# quad87.net
KiCad netlist of a schematic drawn in EAGLE
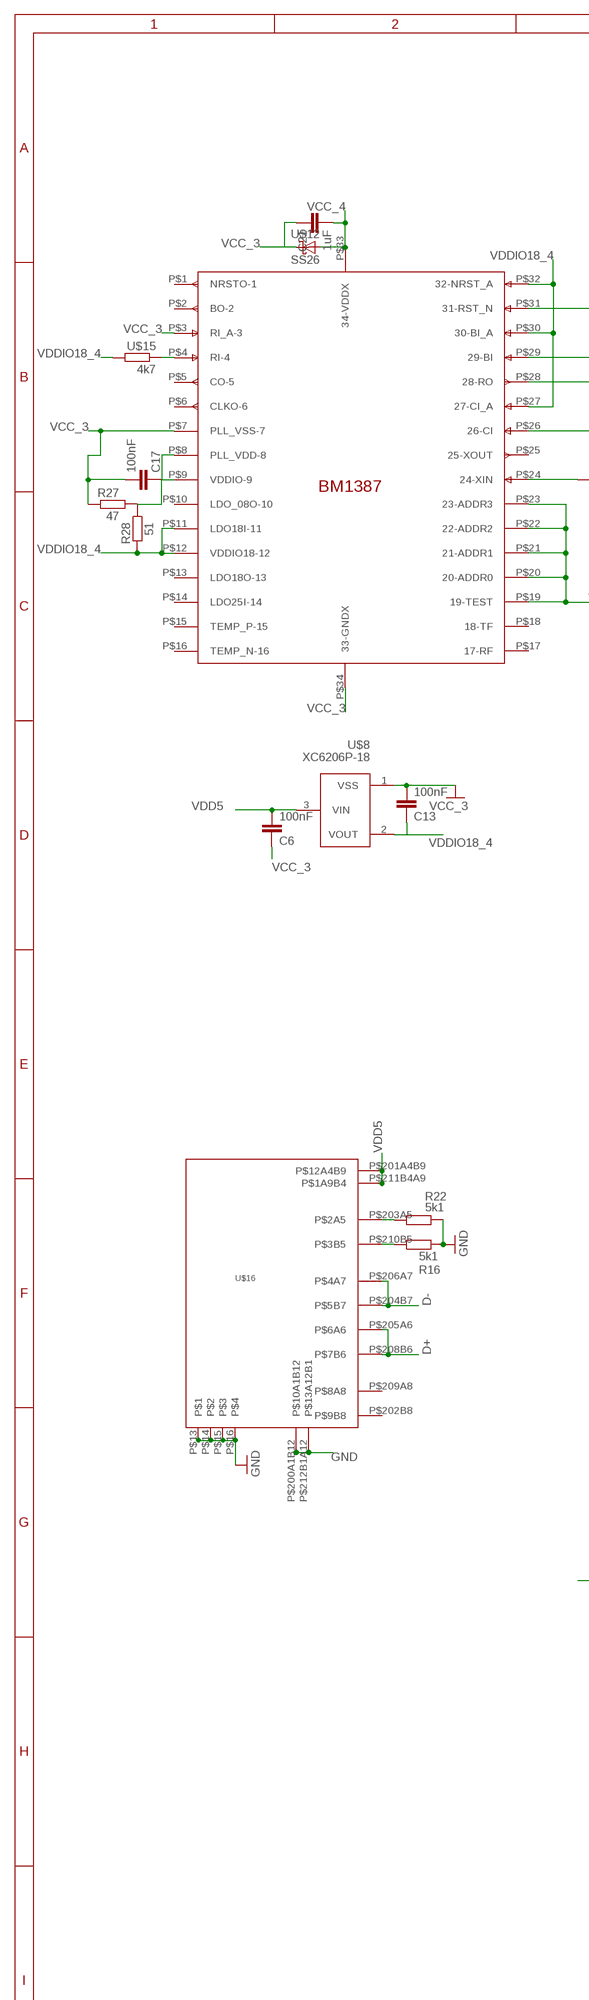
[diagram p0: schematic, sheet 1, part 1 of 2]
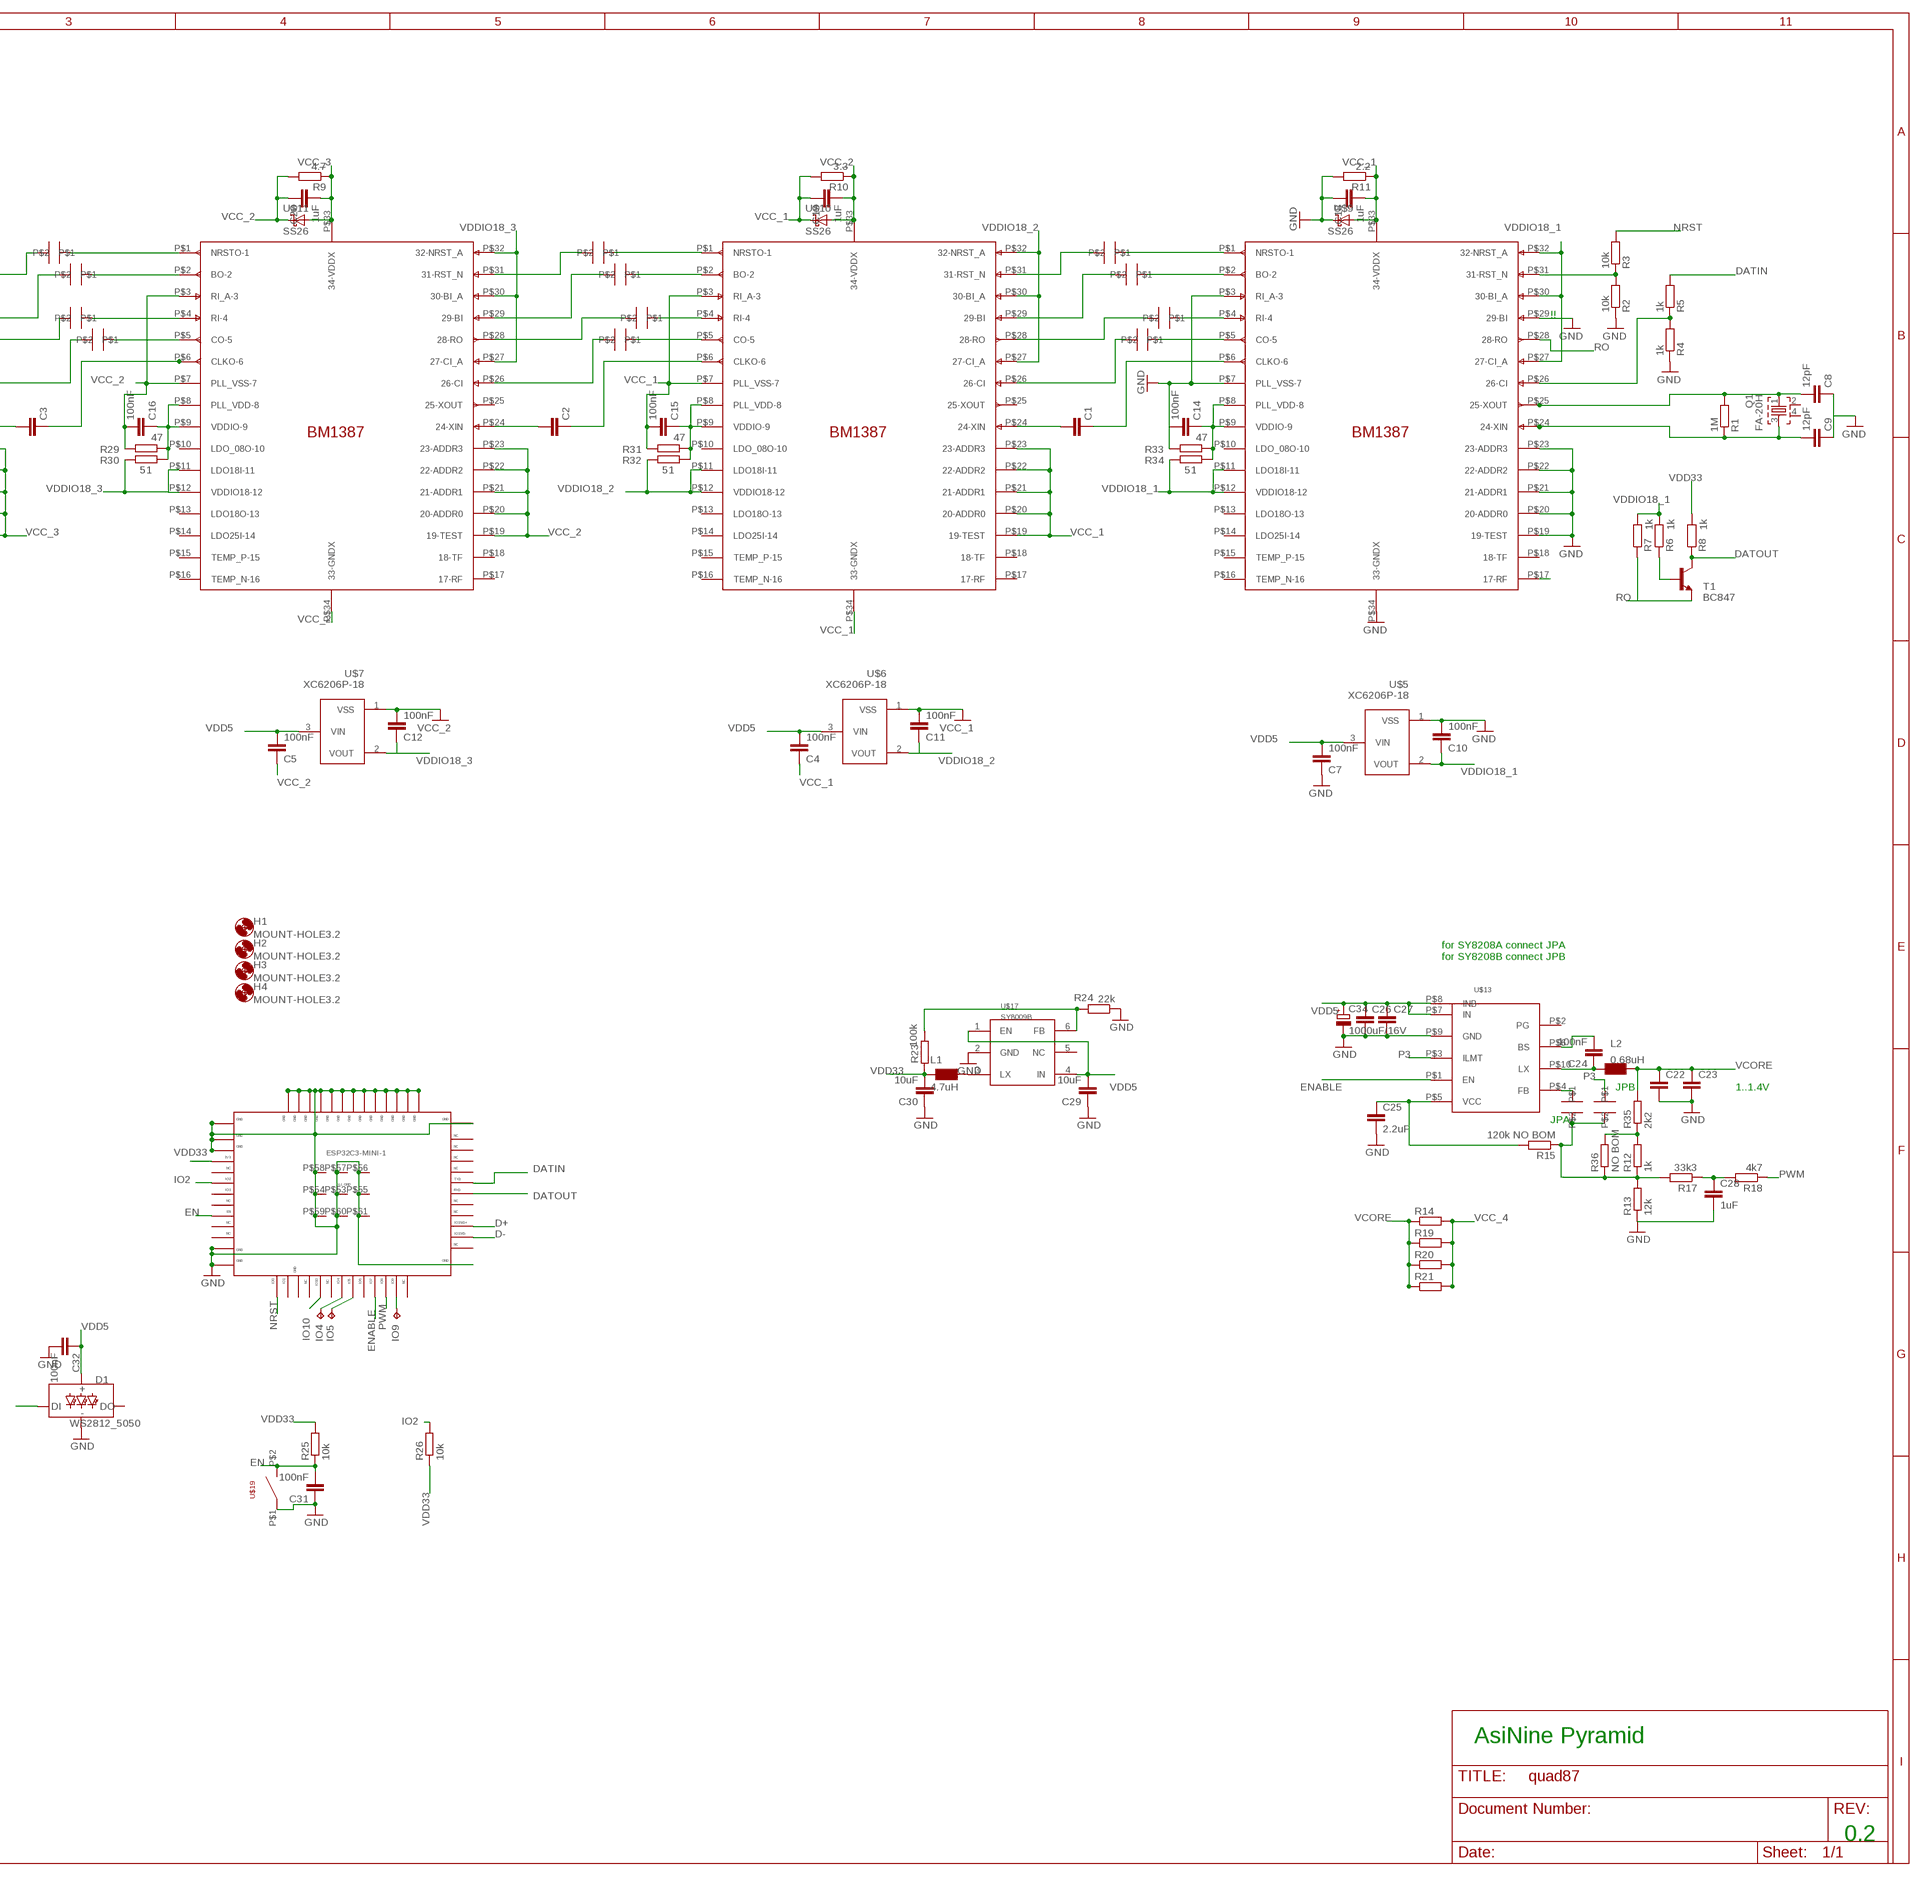
[diagram p1: schematic, sheet 1, part 2 of 2]

(export (version "E")
  (design (tool "Eeschema 10.0.6"))
  (components
    (comp (ref "C1")
      (value "C-EUC0402")
      (footprint "eagle-import:C0402")
      (libsource (lib "eagle-import") (part "C-EUC0402"))
    )
    (comp (ref "C2")
      (value "C-EUC0402")
      (footprint "eagle-import:C0402")
      (libsource (lib "eagle-import") (part "C-EUC0402"))
    )
    (comp (ref "C3")
      (value "C-EUC0402")
      (footprint "eagle-import:C0402")
      (libsource (lib "eagle-import") (part "C-EUC0402"))
    )
    (comp (ref "C4")
      (value "100nF")
      (footprint "eagle-import:C0603")
      (libsource (lib "eagle-import") (part "C-EUC0603"))
    )
    (comp (ref "C5")
      (value "100nF")
      (footprint "eagle-import:C0603")
      (libsource (lib "eagle-import") (part "C-EUC0603"))
    )
    (comp (ref "C6")
      (value "100nF")
      (footprint "eagle-import:C0603")
      (libsource (lib "eagle-import") (part "C-EUC0603"))
    )
    (comp (ref "C7")
      (value "100nF")
      (footprint "eagle-import:C0603")
      (libsource (lib "eagle-import") (part "C-EUC0603"))
    )
    (comp (ref "C8")
      (value "12pF")
      (footprint "eagle-import:C0402")
      (libsource (lib "eagle-import") (part "C-EUC0402"))
    )
    (comp (ref "C9")
      (value "12pF")
      (footprint "eagle-import:C0402")
      (libsource (lib "eagle-import") (part "C-EUC0402"))
    )
    (comp (ref "C10")
      (value "100nF")
      (footprint "eagle-import:C0603")
      (libsource (lib "eagle-import") (part "C-EUC0603"))
    )
    (comp (ref "C11")
      (value "100nF")
      (footprint "eagle-import:C0603")
      (libsource (lib "eagle-import") (part "C-EUC0603"))
    )
    (comp (ref "C12")
      (value "100nF")
      (footprint "eagle-import:C0603")
      (libsource (lib "eagle-import") (part "C-EUC0603"))
    )
    (comp (ref "C13")
      (value "100nF")
      (footprint "eagle-import:C0603")
      (libsource (lib "eagle-import") (part "C-EUC0603"))
    )
    (comp (ref "C14")
      (value "100nF")
      (footprint "eagle-import:C0402")
      (libsource (lib "eagle-import") (part "C-EUC0402"))
    )
    (comp (ref "C15")
      (value "100nF")
      (footprint "eagle-import:C0402")
      (libsource (lib "eagle-import") (part "C-EUC0402"))
    )
    (comp (ref "C16")
      (value "100nF")
      (footprint "eagle-import:C0402")
      (libsource (lib "eagle-import") (part "C-EUC0402"))
    )
    (comp (ref "C17")
      (value "100nF")
      (footprint "eagle-import:C0402")
      (libsource (lib "eagle-import") (part "C-EUC0402"))
    )
    (comp (ref "C18")
      (value "1uF")
      (footprint "eagle-import:C0603")
      (libsource (lib "eagle-import") (part "C-EUC0603"))
    )
    (comp (ref "C19")
      (value "1uF")
      (footprint "eagle-import:C0603")
      (libsource (lib "eagle-import") (part "C-EUC0603"))
    )
    (comp (ref "C20")
      (value "1uF")
      (footprint "eagle-import:C0603")
      (libsource (lib "eagle-import") (part "C-EUC0603"))
    )
    (comp (ref "C21")
      (value "1uF")
      (footprint "eagle-import:C0603")
      (libsource (lib "eagle-import") (part "C-EUC0603"))
    )
    (comp (ref "C22")
      (value "C-EUC1210K")
      (footprint "eagle-import:C1210K")
      (libsource (lib "eagle-import") (part "C-EUC1210K"))
    )
    (comp (ref "C23")
      (value "C-EUC1210K")
      (footprint "eagle-import:C1210K")
      (libsource (lib "eagle-import") (part "C-EUC1210K"))
    )
    (comp (ref "C24")
      (value "100nF")
      (footprint "eagle-import:C0603")
      (libsource (lib "eagle-import") (part "C-EUC0603"))
    )
    (comp (ref "C25")
      (value "2.2uF")
      (footprint "eagle-import:C0603")
      (libsource (lib "eagle-import") (part "C-EUC0603"))
    )
    (comp (ref "C26")
      (value "C-EUC0805")
      (footprint "eagle-import:C0805")
      (libsource (lib "eagle-import") (part "C-EUC0805"))
    )
    (comp (ref "C27")
      (value "C-EUC0805")
      (footprint "eagle-import:C0805")
      (libsource (lib "eagle-import") (part "C-EUC0805"))
    )
    (comp (ref "C28")
      (value "1uF")
      (footprint "eagle-import:C0603")
      (libsource (lib "eagle-import") (part "C-EUC0603"))
    )
    (comp (ref "C29")
      (value "10uF")
      (footprint "eagle-import:C0603")
      (libsource (lib "eagle-import") (part "C-EUC0603"))
    )
    (comp (ref "C30")
      (value "10uF")
      (footprint "eagle-import:C0603")
      (libsource (lib "eagle-import") (part "C-EUC0603"))
    )
    (comp (ref "C31")
      (value "100nF")
      (footprint "eagle-import:C0603")
      (libsource (lib "eagle-import") (part "C-EUC0603"))
    )
    (comp (ref "C32")
      (value "100nF")
      (footprint "eagle-import:C0603")
      (libsource (lib "eagle-import") (part "C-EUC0603"))
    )
    (comp (ref "C34")
      (value "1000uF/16V")
      (footprint "eagle-import:TT5D10")
      (libsource (lib "eagle-import") (part "CPOL-EUTT5D10"))
    )
    (comp (ref "D1")
      (value "WS2812_5050")
      (footprint "eagle-import:WS2812-5X5-4PIN")
      (libsource (lib "eagle-import") (part "WS2812_5050"))
    )
    (comp (ref "ESP32C3-MINI-1")
      (value "ESP32-C3-MINI-1")
      (footprint "eagle-import:ESP32C3MINI")
      (libsource (lib "eagle-import") (part "ESP32C3MINI"))
    )
    (comp (ref "H1")
      (value "MOUNT-HOLE3.2")
      (footprint "eagle-import:3,2")
      (libsource (lib "eagle-import") (part "MOUNT-HOLE3.2"))
    )
    (comp (ref "H2")
      (value "MOUNT-HOLE3.2")
      (footprint "eagle-import:3,2")
      (libsource (lib "eagle-import") (part "MOUNT-HOLE3.2"))
    )
    (comp (ref "H3")
      (value "MOUNT-HOLE3.2")
      (footprint "eagle-import:3,2")
      (libsource (lib "eagle-import") (part "MOUNT-HOLE3.2"))
    )
    (comp (ref "H4")
      (value "MOUNT-HOLE3.2")
      (footprint "eagle-import:3,2")
      (libsource (lib "eagle-import") (part "MOUNT-HOLE3.2"))
    )
    (comp (ref "IO4")
      (value "TPB1,27")
      (footprint "eagle-import:B1,27")
      (libsource (lib "eagle-import") (part "TPB1,27"))
    )
    (comp (ref "IO5")
      (value "TPB1,27")
      (footprint "eagle-import:B1,27")
      (libsource (lib "eagle-import") (part "TPB1,27"))
    )
    (comp (ref "IO9")
      (value "TPB1,27")
      (footprint "eagle-import:B1,27")
      (libsource (lib "eagle-import") (part "TPB1,27"))
    )
    (comp (ref "JPA")
      (value "SOLDERJUMPER")
      (footprint "eagle-import:SOLDERJUMPER")
      (libsource (lib "eagle-import") (part "SOLDERJUMPER"))
    )
    (comp (ref "JPB")
      (value "SOLDERJUMPER")
      (footprint "eagle-import:SOLDERJUMPER")
      (libsource (lib "eagle-import") (part "SOLDERJUMPER"))
    )
    (comp (ref "L1")
      (value "4.7uH")
      (footprint "eagle-import:L0420")
      (libsource (lib "eagle-import") (part "L0420"))
    )
    (comp (ref "L2")
      (value "0.68uH")
      (footprint "eagle-import:L0630")
      (libsource (lib "eagle-import") (part "L0630"))
    )
    (comp (ref "Q1")
      (value "FA-20H")
      (footprint "eagle-import:FA-20H")
      (libsource (lib "eagle-import") (part "FA-20H"))
    )
    (comp (ref "R1")
      (value "1M")
      (footprint "eagle-import:R0402")
      (libsource (lib "eagle-import") (part "R-EU_R0402"))
    )
    (comp (ref "R2")
      (value "10k")
      (footprint "eagle-import:R0402")
      (libsource (lib "eagle-import") (part "R-EU_R0402"))
    )
    (comp (ref "R3")
      (value "10k")
      (footprint "eagle-import:R0402")
      (libsource (lib "eagle-import") (part "R-EU_R0402"))
    )
    (comp (ref "R4")
      (value "1k")
      (footprint "eagle-import:R0603")
      (libsource (lib "eagle-import") (part "R-EU_R0603"))
    )
    (comp (ref "R5")
      (value "1k")
      (footprint "eagle-import:R0603")
      (libsource (lib "eagle-import") (part "R-EU_R0603"))
    )
    (comp (ref "R6")
      (value "1k")
      (footprint "eagle-import:R0603")
      (libsource (lib "eagle-import") (part "R-EU_R0603"))
    )
    (comp (ref "R7")
      (value "1k")
      (footprint "eagle-import:R0603")
      (libsource (lib "eagle-import") (part "R-EU_R0603"))
    )
    (comp (ref "R8")
      (value "1k")
      (footprint "eagle-import:R0603")
      (libsource (lib "eagle-import") (part "R-EU_R0603"))
    )
    (comp (ref "R9")
      (value "4.7")
      (footprint "eagle-import:R0603")
      (libsource (lib "eagle-import") (part "R-EU_R0603"))
    )
    (comp (ref "R10")
      (value "3.3")
      (footprint "eagle-import:R0603")
      (libsource (lib "eagle-import") (part "R-EU_R0603"))
    )
    (comp (ref "R11")
      (value "2.2")
      (footprint "eagle-import:R0603")
      (libsource (lib "eagle-import") (part "R-EU_R0603"))
    )
    (comp (ref "R12")
      (value "1k")
      (footprint "eagle-import:R0603")
      (libsource (lib "eagle-import") (part "R-EU_R0603"))
    )
    (comp (ref "R13")
      (value "12k")
      (footprint "eagle-import:R0603")
      (libsource (lib "eagle-import") (part "R-EU_R0603"))
    )
    (comp (ref "R14")
      (value "R-EU_R2010")
      (footprint "eagle-import:R2010")
      (libsource (lib "eagle-import") (part "R-EU_R2010"))
    )
    (comp (ref "R15")
      (value "120k NO BOM")
      (footprint "eagle-import:R0603")
      (libsource (lib "eagle-import") (part "R-EU_R0603"))
    )
    (comp (ref "R16")
      (value "5k1")
      (footprint "eagle-import:R0402")
      (libsource (lib "eagle-import") (part "R-EU_R0402"))
    )
    (comp (ref "R17")
      (value "33k3")
      (footprint "eagle-import:R0603")
      (libsource (lib "eagle-import") (part "R-EU_R0603"))
    )
    (comp (ref "R18")
      (value "4k7")
      (footprint "eagle-import:R0603")
      (libsource (lib "eagle-import") (part "R-EU_R0603"))
    )
    (comp (ref "R19")
      (value "R-EU_R2010")
      (footprint "eagle-import:R2010")
      (libsource (lib "eagle-import") (part "R-EU_R2010"))
    )
    (comp (ref "R20")
      (value "R-EU_R2010")
      (footprint "eagle-import:R2010")
      (libsource (lib "eagle-import") (part "R-EU_R2010"))
    )
    (comp (ref "R21")
      (value "R-EU_R2010")
      (footprint "eagle-import:R2010")
      (libsource (lib "eagle-import") (part "R-EU_R2010"))
    )
    (comp (ref "R22")
      (value "5k1")
      (footprint "eagle-import:R0402")
      (libsource (lib "eagle-import") (part "R-EU_R0402"))
    )
    (comp (ref "R23")
      (value "100k")
      (footprint "eagle-import:R0603")
      (libsource (lib "eagle-import") (part "R-EU_R0603"))
    )
    (comp (ref "R24")
      (value "22k")
      (footprint "eagle-import:R0603")
      (libsource (lib "eagle-import") (part "R-EU_R0603"))
    )
    (comp (ref "R25")
      (value "10k")
      (footprint "eagle-import:R0603")
      (libsource (lib "eagle-import") (part "R-EU_R0603"))
    )
    (comp (ref "R26")
      (value "10k")
      (footprint "eagle-import:R0603")
      (libsource (lib "eagle-import") (part "R-EU_R0603"))
    )
    (comp (ref "R27")
      (value "47")
      (footprint "eagle-import:R0402")
      (libsource (lib "eagle-import") (part "R-EU_R0402"))
    )
    (comp (ref "R28")
      (value "51")
      (footprint "eagle-import:R0402")
      (libsource (lib "eagle-import") (part "R-EU_R0402"))
    )
    (comp (ref "R29")
      (value "47")
      (footprint "eagle-import:R0402")
      (libsource (lib "eagle-import") (part "R-EU_R0402"))
    )
    (comp (ref "R30")
      (value "51")
      (footprint "eagle-import:R0402")
      (libsource (lib "eagle-import") (part "R-EU_R0402"))
    )
    (comp (ref "R31")
      (value "47")
      (footprint "eagle-import:R0402")
      (libsource (lib "eagle-import") (part "R-EU_R0402"))
    )
    (comp (ref "R32")
      (value "51")
      (footprint "eagle-import:R0402")
      (libsource (lib "eagle-import") (part "R-EU_R0402"))
    )
    (comp (ref "R33")
      (value "47")
      (footprint "eagle-import:R0402")
      (libsource (lib "eagle-import") (part "R-EU_R0402"))
    )
    (comp (ref "R34")
      (value "51")
      (footprint "eagle-import:R0402")
      (libsource (lib "eagle-import") (part "R-EU_R0402"))
    )
    (comp (ref "R35")
      (value "2k2")
      (footprint "eagle-import:R0603")
      (libsource (lib "eagle-import") (part "R-EU_R0603"))
    )
    (comp (ref "R36")
      (value "NO BOM")
      (footprint "eagle-import:R0603")
      (libsource (lib "eagle-import") (part "R-EU_R0603"))
    )
    (comp (ref "T1")
      (value "BC847")
      (footprint "eagle-import:SOT23")
      (libsource (lib "eagle-import") (part "BC847"))
    )
    (comp (ref "U$1")
      (value "BM1387A")
      (footprint "eagle-import:BM1391")
      (libsource (lib "eagle-import") (part "BM1387A"))
    )
    (comp (ref "U$2")
      (value "BM1387A")
      (footprint "eagle-import:BM1391")
      (libsource (lib "eagle-import") (part "BM1387A"))
    )
    (comp (ref "U$3")
      (value "BM1387A")
      (footprint "eagle-import:BM1391")
      (libsource (lib "eagle-import") (part "BM1387A"))
    )
    (comp (ref "U$4")
      (value "BM1387A")
      (footprint "eagle-import:BM1391")
      (libsource (lib "eagle-import") (part "BM1387A"))
    )
    (comp (ref "U$5")
      (value "XC6206P-18")
      (footprint "eagle-import:SOT23")
      (libsource (lib "eagle-import") (part "XC6206P"))
    )
    (comp (ref "U$6")
      (value "XC6206P-18")
      (footprint "eagle-import:SOT23")
      (libsource (lib "eagle-import") (part "XC6206P"))
    )
    (comp (ref "U$7")
      (value "XC6206P-18")
      (footprint "eagle-import:SOT23")
      (libsource (lib "eagle-import") (part "XC6206P"))
    )
    (comp (ref "U$8")
      (value "XC6206P-18")
      (footprint "eagle-import:SOT23")
      (libsource (lib "eagle-import") (part "XC6206P"))
    )
    (comp (ref "U$9")
      (value "SS26")
      (footprint "eagle-import:SS26")
      (libsource (lib "eagle-import") (part "SS26"))
    )
    (comp (ref "U$10")
      (value "SS26")
      (footprint "eagle-import:SS26")
      (libsource (lib "eagle-import") (part "SS26"))
    )
    (comp (ref "U$11")
      (value "SS26")
      (footprint "eagle-import:SS26")
      (libsource (lib "eagle-import") (part "SS26"))
    )
    (comp (ref "U$12")
      (value "SS26")
      (footprint "eagle-import:SS26")
      (libsource (lib "eagle-import") (part "SS26"))
    )
    (comp (ref "U$13")
      (value "SY8208")
      (footprint "eagle-import:SY8208")
      (libsource (lib "eagle-import") (part "SY8208"))
    )
    (comp (ref "U$15")
      (value "4k7")
      (footprint "eagle-import:R0603")
      (libsource (lib "eagle-import") (part "R0603"))
    )
    (comp (ref "U$16")
      (value "USBCTHT")
      (footprint "eagle-import:USBCSMTTHT")
      (libsource (lib "eagle-import") (part "USBCTHT"))
    )
    (comp (ref "U$17")
      (value "SY8009B")
      (footprint "eagle-import:SOT23-6")
      (libsource (lib "eagle-import") (part "SY8009B"))
    )
    (comp (ref "U$19")
      (value "SMDSW6X3")
      (footprint "eagle-import:SW6X3")
      (libsource (lib "eagle-import") (part "SMDSW6X3"))
    )
    (comp (ref "U$20")
      (value "SOLDERJUMPER")
      (footprint "eagle-import:SOLDERJUMPER")
      (libsource (lib "eagle-import") (part "SOLDERJUMPER"))
    )
    (comp (ref "U$21")
      (value "SOLDERJUMPER")
      (footprint "eagle-import:SOLDERJUMPER")
      (libsource (lib "eagle-import") (part "SOLDERJUMPER"))
    )
    (comp (ref "U$22")
      (value "SOLDERJUMPER")
      (footprint "eagle-import:SOLDERJUMPER")
      (libsource (lib "eagle-import") (part "SOLDERJUMPER"))
    )
    (comp (ref "U$23")
      (value "SOLDERJUMPER")
      (footprint "eagle-import:SOLDERJUMPER")
      (libsource (lib "eagle-import") (part "SOLDERJUMPER"))
    )
    (comp (ref "U$24")
      (value "SOLDERJUMPER")
      (footprint "eagle-import:SOLDERJUMPER")
      (libsource (lib "eagle-import") (part "SOLDERJUMPER"))
    )
    (comp (ref "U$25")
      (value "SOLDERJUMPER")
      (footprint "eagle-import:SOLDERJUMPER")
      (libsource (lib "eagle-import") (part "SOLDERJUMPER"))
    )
    (comp (ref "U$26")
      (value "SOLDERJUMPER")
      (footprint "eagle-import:SOLDERJUMPER")
      (libsource (lib "eagle-import") (part "SOLDERJUMPER"))
    )
    (comp (ref "U$28")
      (value "SOLDERJUMPER")
      (footprint "eagle-import:SOLDERJUMPER")
      (libsource (lib "eagle-import") (part "SOLDERJUMPER"))
    )
    (comp (ref "U$29")
      (value "SOLDERJUMPER")
      (footprint "eagle-import:SOLDERJUMPER")
      (libsource (lib "eagle-import") (part "SOLDERJUMPER"))
    )
    (comp (ref "U$30")
      (value "SOLDERJUMPER")
      (footprint "eagle-import:SOLDERJUMPER")
      (libsource (lib "eagle-import") (part "SOLDERJUMPER"))
    )
    (comp (ref "U$31")
      (value "SOLDERJUMPER")
      (footprint "eagle-import:SOLDERJUMPER")
      (libsource (lib "eagle-import") (part "SOLDERJUMPER"))
    )
    (comp (ref "U$32")
      (value "SOLDERJUMPER")
      (footprint "eagle-import:SOLDERJUMPER")
      (libsource (lib "eagle-import") (part "SOLDERJUMPER"))
    )
  )
  (nets
    (net (code "1") (name "/D+") (class "Default")
      (node (ref "ESP32C3-MINI-1") (pin "P$27") (pinfunction "P$27_P$27") (pintype "bidirectional"))
      (node (ref "U$16") (pin "P$205A6") (pinfunction "P$6A6_P$205A6") (pintype "bidirectional"))
      (node (ref "U$16") (pin "P$208B6") (pinfunction "P$7B6_P$208B6") (pintype "bidirectional"))
    )
    (net (code "2") (name "/D-") (class "Default")
      (node (ref "ESP32C3-MINI-1") (pin "P$26") (pinfunction "P$26_P$26") (pintype "bidirectional"))
      (node (ref "U$16") (pin "P$204B7") (pinfunction "P$5B7_P$204B7") (pintype "bidirectional"))
      (node (ref "U$16") (pin "P$206A7") (pinfunction "P$4A7_P$206A7") (pintype "bidirectional"))
    )
    (net (code "3") (name "/DATIN") (class "Default")
      (node (ref "ESP32C3-MINI-1") (pin "P$31") (pinfunction "P$31_P$31") (pintype "bidirectional"))
      (node (ref "R5") (pin "2") (pinfunction "2_2") (pintype "passive"))
    )
    (net (code "4") (name "/DATOUT") (class "Default")
      (node (ref "ESP32C3-MINI-1") (pin "P$30") (pinfunction "P$30_P$30") (pintype "bidirectional"))
      (node (ref "R8") (pin "1") (pinfunction "1_1") (pintype "passive"))
      (node (ref "T1") (pin "3") (pinfunction "C_3") (pintype "passive"))
    )
    (net (code "5") (name "/EN") (class "Default")
      (node (ref "C31") (pin "2") (pinfunction "2_2") (pintype "passive"))
      (node (ref "ESP32C3-MINI-1") (pin "P$8") (pinfunction "P$8_P$8") (pintype "bidirectional"))
      (node (ref "R25") (pin "1") (pinfunction "1_1") (pintype "passive"))
      (node (ref "U$19") (pin "P$2") (pinfunction "P$2_P$2") (pintype "bidirectional"))
    )
    (net (code "6") (name "/ENABLE") (class "Default")
      (node (ref "ESP32C3-MINI-1") (pin "P$21") (pinfunction "P$21_P$21") (pintype "bidirectional"))
      (node (ref "U$13") (pin "P$1") (pinfunction "EN_P$1") (pintype "bidirectional"))
    )
    (net (code "7") (name "/IO2") (class "Default")
      (node (ref "ESP32C3-MINI-1") (pin "P$5") (pinfunction "P$5_P$5") (pintype "bidirectional"))
      (node (ref "R26") (pin "2") (pinfunction "2_2") (pintype "passive"))
    )
    (net (code "8") (name "/IO10") (class "Default")
      (node (ref "D1") (pin "DI") (pinfunction "DI_DI") (pintype "bidirectional"))
      (node (ref "ESP32C3-MINI-1") (pin "P$16") (pinfunction "P$16_P$16") (pintype "bidirectional"))
    )
    (net (code "9") (name "/NRST") (class "Default")
      (node (ref "ESP32C3-MINI-1") (pin "P$12") (pinfunction "P$12_P$12") (pintype "bidirectional"))
      (node (ref "R3") (pin "2") (pinfunction "2_2") (pintype "passive"))
    )
    (net (code "10") (name "/P3") (class "Default")
      (node (ref "JPB") (pin "P$2") (pinfunction "P$2_P$2") (pintype "bidirectional"))
      (node (ref "U$13") (pin "P$3") (pinfunction "ILMT_P$3") (pintype "bidirectional"))
    )
    (net (code "11") (name "/PWM") (class "Default")
      (node (ref "ESP32C3-MINI-1") (pin "P$22") (pinfunction "P$22_P$22") (pintype "bidirectional"))
      (node (ref "R18") (pin "1") (pinfunction "1_1") (pintype "passive"))
    )
    (net (code "12") (name "/RO") (class "Default")
      (node (ref "R7") (pin "1") (pinfunction "1_1") (pintype "passive"))
      (node (ref "T1") (pin "2") (pinfunction "E_2") (pintype "passive"))
      (node (ref "U$1") (pin "P$28") (pinfunction "28-RO_P$28") (pintype "bidirectional"))
    )
    (net (code "13") (name "/VCC_4") (class "Default")
      (node (ref "C21") (pin "2") (pinfunction "2_2") (pintype "passive"))
      (node (ref "R14") (pin "2") (pinfunction "2_2") (pintype "passive"))
      (node (ref "R19") (pin "2") (pinfunction "2_2") (pintype "passive"))
      (node (ref "R20") (pin "2") (pinfunction "2_2") (pintype "passive"))
      (node (ref "R21") (pin "2") (pinfunction "2_2") (pintype "passive"))
      (node (ref "U$12") (pin "P$1") (pinfunction "A_P$1") (pintype "passive"))
      (node (ref "U$4") (pin "P$33") (pinfunction "34-VDDX_P$33") (pintype "bidirectional"))
    )
    (net (code "14") (name "/VCORE") (class "Default")
      (node (ref "C22") (pin "1") (pinfunction "1_1") (pintype "passive"))
      (node (ref "C23") (pin "1") (pinfunction "1_1") (pintype "passive"))
      (node (ref "L2") (pin "P$2") (pinfunction "2_P$2") (pintype "passive"))
      (node (ref "R14") (pin "1") (pinfunction "1_1") (pintype "passive"))
      (node (ref "R19") (pin "1") (pinfunction "1_1") (pintype "passive"))
      (node (ref "R20") (pin "1") (pinfunction "1_1") (pintype "passive"))
      (node (ref "R21") (pin "1") (pinfunction "1_1") (pintype "passive"))
      (node (ref "R35") (pin "2") (pinfunction "2_2") (pintype "passive"))
    )
    (net (code "15") (name "/VDD5") (class "Default")
      (node (ref "C26") (pin "1") (pinfunction "1_1") (pintype "passive"))
      (node (ref "C27") (pin "1") (pinfunction "1_1") (pintype "passive"))
      (node (ref "C29") (pin "2") (pinfunction "2_2") (pintype "passive"))
      (node (ref "C32") (pin "1") (pinfunction "1_1") (pintype "passive"))
      (node (ref "C34") (pin "+") (pinfunction "+_+") (pintype "passive"))
      (node (ref "C4") (pin "2") (pinfunction "2_2") (pintype "passive"))
      (node (ref "C5") (pin "2") (pinfunction "2_2") (pintype "passive"))
      (node (ref "C6") (pin "2") (pinfunction "2_2") (pintype "passive"))
      (node (ref "C7") (pin "2") (pinfunction "2_2") (pintype "passive"))
      (node (ref "D1") (pin "VCC") (pinfunction "VCC_VCC") (pintype "bidirectional"))
      (node (ref "U$13") (pin "P$7") (pinfunction "IN_P$7") (pintype "bidirectional"))
      (node (ref "U$13") (pin "P$8") (pinfunction "INB_P$8") (pintype "bidirectional"))
      (node (ref "U$16") (pin "P$201A4B9") (pinfunction "P$12A4B9_P$201A4B9") (pintype "bidirectional"))
      (node (ref "U$16") (pin "P$211B4A9") (pinfunction "P$1A9B4_P$211B4A9") (pintype "bidirectional"))
      (node (ref "U$17") (pin "1") (pinfunction "EN_1") (pintype "bidirectional"))
      (node (ref "U$17") (pin "4") (pinfunction "IN_4") (pintype "bidirectional"))
      (node (ref "U$5") (pin "3") (pinfunction "VIN_3") (pintype "bidirectional"))
      (node (ref "U$6") (pin "3") (pinfunction "VIN_3") (pintype "bidirectional"))
      (node (ref "U$7") (pin "3") (pinfunction "VIN_3") (pintype "bidirectional"))
      (node (ref "U$8") (pin "3") (pinfunction "VIN_3") (pintype "bidirectional"))
    )
    (net (code "16") (name "/VDD33") (class "Default")
      (node (ref "C30") (pin "2") (pinfunction "2_2") (pintype "passive"))
      (node (ref "ESP32C3-MINI-1") (pin "P$3") (pinfunction "P$3_P$3") (pintype "bidirectional"))
      (node (ref "L1") (pin "P$1") (pinfunction "1_P$1") (pintype "passive"))
      (node (ref "R23") (pin "1") (pinfunction "1_1") (pintype "passive"))
      (node (ref "R25") (pin "2") (pinfunction "2_2") (pintype "passive"))
      (node (ref "R26") (pin "1") (pinfunction "1_1") (pintype "passive"))
      (node (ref "R8") (pin "2") (pinfunction "2_2") (pintype "passive"))
    )
    (net (code "17") (name "/VDDIO18_1") (class "Default")
      (node (ref "C10") (pin "1") (pinfunction "1_1") (pintype "passive"))
      (node (ref "R34") (pin "2") (pinfunction "2_2") (pintype "passive"))
      (node (ref "R6") (pin "2") (pinfunction "2_2") (pintype "passive"))
      (node (ref "R7") (pin "2") (pinfunction "2_2") (pintype "passive"))
      (node (ref "U$1") (pin "P$11") (pinfunction "LDO18I-11_P$11") (pintype "bidirectional"))
      (node (ref "U$1") (pin "P$12") (pinfunction "VDDIO18-12_P$12") (pintype "bidirectional"))
      (node (ref "U$1") (pin "P$27") (pinfunction "27-CI_A_P$27") (pintype "bidirectional"))
      (node (ref "U$1") (pin "P$30") (pinfunction "30-BI_A_P$30") (pintype "bidirectional"))
      (node (ref "U$1") (pin "P$32") (pinfunction "32-NRST_A_P$32") (pintype "bidirectional"))
      (node (ref "U$5") (pin "2") (pinfunction "VOUT_2") (pintype "bidirectional"))
    )
    (net (code "18") (name "/VDDIO18_2") (class "Default")
      (node (ref "C11") (pin "1") (pinfunction "1_1") (pintype "passive"))
      (node (ref "R32") (pin "2") (pinfunction "2_2") (pintype "passive"))
      (node (ref "U$2") (pin "P$11") (pinfunction "LDO18I-11_P$11") (pintype "bidirectional"))
      (node (ref "U$2") (pin "P$12") (pinfunction "VDDIO18-12_P$12") (pintype "bidirectional"))
      (node (ref "U$2") (pin "P$27") (pinfunction "27-CI_A_P$27") (pintype "bidirectional"))
      (node (ref "U$2") (pin "P$30") (pinfunction "30-BI_A_P$30") (pintype "bidirectional"))
      (node (ref "U$2") (pin "P$32") (pinfunction "32-NRST_A_P$32") (pintype "bidirectional"))
      (node (ref "U$6") (pin "2") (pinfunction "VOUT_2") (pintype "bidirectional"))
    )
    (net (code "19") (name "/VDDIO18_3") (class "Default")
      (node (ref "C12") (pin "1") (pinfunction "1_1") (pintype "passive"))
      (node (ref "R30") (pin "2") (pinfunction "2_2") (pintype "passive"))
      (node (ref "U$3") (pin "P$11") (pinfunction "LDO18I-11_P$11") (pintype "bidirectional"))
      (node (ref "U$3") (pin "P$12") (pinfunction "VDDIO18-12_P$12") (pintype "bidirectional"))
      (node (ref "U$3") (pin "P$27") (pinfunction "27-CI_A_P$27") (pintype "bidirectional"))
      (node (ref "U$3") (pin "P$30") (pinfunction "30-BI_A_P$30") (pintype "bidirectional"))
      (node (ref "U$3") (pin "P$32") (pinfunction "32-NRST_A_P$32") (pintype "bidirectional"))
      (node (ref "U$7") (pin "2") (pinfunction "VOUT_2") (pintype "bidirectional"))
    )
    (net (code "20") (name "/VDDIO18_4") (class "Default")
      (node (ref "C13") (pin "1") (pinfunction "1_1") (pintype "passive"))
      (node (ref "R28") (pin "2") (pinfunction "2_2") (pintype "passive"))
      (node (ref "U$15") (pin "2") (pinfunction "2_2") (pintype "passive"))
      (node (ref "U$4") (pin "P$11") (pinfunction "LDO18I-11_P$11") (pintype "bidirectional"))
      (node (ref "U$4") (pin "P$12") (pinfunction "VDDIO18-12_P$12") (pintype "bidirectional"))
      (node (ref "U$4") (pin "P$27") (pinfunction "27-CI_A_P$27") (pintype "bidirectional"))
      (node (ref "U$4") (pin "P$30") (pinfunction "30-BI_A_P$30") (pintype "bidirectional"))
      (node (ref "U$4") (pin "P$32") (pinfunction "32-NRST_A_P$32") (pintype "bidirectional"))
      (node (ref "U$8") (pin "2") (pinfunction "VOUT_2") (pintype "bidirectional"))
    )
    (net (code "21") (name "GND") (class "Default")
      (node (ref "C10") (pin "2") (pinfunction "2_2") (pintype "passive"))
      (node (ref "C14") (pin "2") (pinfunction "2_2") (pintype "passive"))
      (node (ref "C18") (pin "1") (pinfunction "1_1") (pintype "passive"))
      (node (ref "C22") (pin "2") (pinfunction "2_2") (pintype "passive"))
      (node (ref "C23") (pin "2") (pinfunction "2_2") (pintype "passive"))
      (node (ref "C25") (pin "2") (pinfunction "2_2") (pintype "passive"))
      (node (ref "C26") (pin "2") (pinfunction "2_2") (pintype "passive"))
      (node (ref "C27") (pin "2") (pinfunction "2_2") (pintype "passive"))
      (node (ref "C28") (pin "2") (pinfunction "2_2") (pintype "passive"))
      (node (ref "C29") (pin "1") (pinfunction "1_1") (pintype "passive"))
      (node (ref "C30") (pin "1") (pinfunction "1_1") (pintype "passive"))
      (node (ref "C31") (pin "1") (pinfunction "1_1") (pintype "passive"))
      (node (ref "C32") (pin "2") (pinfunction "2_2") (pintype "passive"))
      (node (ref "C34") (pin "-") (pinfunction "-_-") (pintype "passive"))
      (node (ref "C7") (pin "1") (pinfunction "1_1") (pintype "passive"))
      (node (ref "C8") (pin "1") (pinfunction "1_1") (pintype "passive"))
      (node (ref "C9") (pin "1") (pinfunction "1_1") (pintype "passive"))
      (node (ref "D1") (pin "GND") (pinfunction "GND_GND") (pintype "bidirectional"))
      (node (ref "ESP32C3-MINI-1") (pin "P$1") (pinfunction "P$1_P$1") (pintype "bidirectional"))
      (node (ref "ESP32C3-MINI-1") (pin "P$11") (pinfunction "P$11_P$11") (pintype "bidirectional"))
      (node (ref "ESP32C3-MINI-1") (pin "P$2") (pinfunction "P$2_P$2") (pintype "bidirectional"))
      (node (ref "ESP32C3-MINI-1") (pin "P$36") (pinfunction "P$36_P$36") (pintype "bidirectional"))
      (node (ref "ESP32C3-MINI-1") (pin "P$37") (pinfunction "P$37_P$37") (pintype "bidirectional"))
      (node (ref "ESP32C3-MINI-1") (pin "P$38") (pinfunction "P$38_P$38") (pintype "bidirectional"))
      (node (ref "ESP32C3-MINI-1") (pin "P$39") (pinfunction "P$39_P$39") (pintype "bidirectional"))
      (node (ref "ESP32C3-MINI-1") (pin "P$40") (pinfunction "P$40_P$40") (pintype "bidirectional"))
      (node (ref "ESP32C3-MINI-1") (pin "P$41") (pinfunction "P$41_P$41") (pintype "bidirectional"))
      (node (ref "ESP32C3-MINI-1") (pin "P$42") (pinfunction "P$42_P$42") (pintype "bidirectional"))
      (node (ref "ESP32C3-MINI-1") (pin "P$43") (pinfunction "P$43_P$43") (pintype "bidirectional"))
      (node (ref "ESP32C3-MINI-1") (pin "P$44") (pinfunction "P$44_P$44") (pintype "bidirectional"))
      (node (ref "ESP32C3-MINI-1") (pin "P$45") (pinfunction "P$45_P$45") (pintype "bidirectional"))
      (node (ref "ESP32C3-MINI-1") (pin "P$46") (pinfunction "P$46_P$46") (pintype "bidirectional"))
      (node (ref "ESP32C3-MINI-1") (pin "P$47") (pinfunction "P$47_P$47") (pintype "bidirectional"))
      (node (ref "ESP32C3-MINI-1") (pin "P$48") (pinfunction "P$48_P$48") (pintype "bidirectional"))
      (node (ref "ESP32C3-MINI-1") (pin "P$49") (pinfunction "P$50_P$49") (pintype "bidirectional"))
      (node (ref "ESP32C3-MINI-1") (pin "P$50") (pinfunction "P$51_P$50") (pintype "bidirectional"))
      (node (ref "ESP32C3-MINI-1") (pin "P$51") (pinfunction "P$52_P$51") (pintype "bidirectional"))
      (node (ref "ESP32C3-MINI-1") (pin "P$52") (pinfunction "P$53_P$52") (pintype "bidirectional"))
      (node (ref "ESP32C3-MINI-1") (pin "P$53") (pinfunction "P$54_P$53") (pintype "bidirectional"))
      (node (ref "ESP32C3-MINI-1") (pin "P$54") (pinfunction "P$55_P$54") (pintype "bidirectional"))
      (node (ref "ESP32C3-MINI-1") (pin "P$55") (pinfunction "P$56_P$55") (pintype "bidirectional"))
      (node (ref "ESP32C3-MINI-1") (pin "P$56") (pinfunction "P$57_P$56") (pintype "bidirectional"))
      (node (ref "ESP32C3-MINI-1") (pin "P$57") (pinfunction "P$58_P$57") (pintype "bidirectional"))
      (node (ref "ESP32C3-MINI-1") (pin "P$58") (pinfunction "P$59_P$58") (pintype "bidirectional"))
      (node (ref "ESP32C3-MINI-1") (pin "P$59") (pinfunction "P$60_P$59") (pintype "bidirectional"))
      (node (ref "ESP32C3-MINI-1") (pin "P$60") (pinfunction "P$61_P$60") (pintype "bidirectional"))
      (node (ref "ESP32C3-MINI-1") (pin "P$61") (pinfunction "P$62_P$61") (pintype "bidirectional"))
      (node (ref "R11") (pin "2") (pinfunction "2_2") (pintype "passive"))
      (node (ref "R13") (pin "1") (pinfunction "1_1") (pintype "passive"))
      (node (ref "R16") (pin "2") (pinfunction "2_2") (pintype "passive"))
      (node (ref "R2") (pin "1") (pinfunction "1_1") (pintype "passive"))
      (node (ref "R22") (pin "2") (pinfunction "2_2") (pintype "passive"))
      (node (ref "R24") (pin "1") (pinfunction "1_1") (pintype "passive"))
      (node (ref "R33") (pin "2") (pinfunction "2_2") (pintype "passive"))
      (node (ref "R4") (pin "1") (pinfunction "1_1") (pintype "passive"))
      (node (ref "U$1") (pin "P$19") (pinfunction "19-TEST_P$19") (pintype "bidirectional"))
      (node (ref "U$1") (pin "P$20") (pinfunction "20-ADDR0_P$20") (pintype "bidirectional"))
      (node (ref "U$1") (pin "P$21") (pinfunction "21-ADDR1_P$21") (pintype "bidirectional"))
      (node (ref "U$1") (pin "P$22") (pinfunction "22-ADDR2_P$22") (pintype "bidirectional"))
      (node (ref "U$1") (pin "P$23") (pinfunction "23-ADDR3_P$23") (pintype "bidirectional"))
      (node (ref "U$1") (pin "P$29") (pinfunction "29-BI_P$29") (pintype "bidirectional"))
      (node (ref "U$1") (pin "P$3") (pinfunction "RI_A-3_P$3") (pintype "bidirectional"))
      (node (ref "U$1") (pin "P$34") (pinfunction "33-GNDX_P$34") (pintype "bidirectional"))
      (node (ref "U$1") (pin "P$7") (pinfunction "PLL_VSS-7_P$7") (pintype "bidirectional"))
      (node (ref "U$13") (pin "P$9") (pinfunction "GND_P$9") (pintype "bidirectional"))
      (node (ref "U$16") (pin "P$13") (pinfunction "P$1_P$13") (pintype "bidirectional"))
      (node (ref "U$16") (pin "P$14") (pinfunction "P$2_P$14") (pintype "bidirectional"))
      (node (ref "U$16") (pin "P$15") (pinfunction "P$3_P$15") (pintype "bidirectional"))
      (node (ref "U$16") (pin "P$16") (pinfunction "P$4_P$16") (pintype "bidirectional"))
      (node (ref "U$16") (pin "P$200A1B12") (pinfunction "P$10A1B12_P$200A1B12") (pintype "bidirectional"))
      (node (ref "U$16") (pin "P$212B1A12") (pinfunction "P$13A12B1_P$212B1A12") (pintype "bidirectional"))
      (node (ref "U$17") (pin "2") (pinfunction "GND_2") (pintype "bidirectional"))
      (node (ref "U$19") (pin "P$1") (pinfunction "P$1_P$1") (pintype "bidirectional"))
      (node (ref "U$5") (pin "1") (pinfunction "VSS_1") (pintype "bidirectional"))
      (node (ref "U$9") (pin "P$2") (pinfunction "C_P$2") (pintype "passive"))
    )
    (net (code "22") (name "Net-(C28-Pad1)") (class "Default")
      (node (ref "C28") (pin "1") (pinfunction "1_1") (pintype "passive"))
      (node (ref "R17") (pin "1") (pinfunction "1_1") (pintype "passive"))
      (node (ref "R18") (pin "2") (pinfunction "2_2") (pintype "passive"))
    )
    (net (code "23") (name "Net-(ESP32C3-MINI-1-PadP$18)") (class "Default")
      (node (ref "ESP32C3-MINI-1") (pin "P$18") (pinfunction "P$18_P$18") (pintype "bidirectional"))
      (node (ref "IO4") (pin "TP") (pinfunction "TP_TP") (pintype "input"))
    )
    (net (code "24") (name "Net-(ESP32C3-MINI-1-PadP$19)") (class "Default")
      (node (ref "ESP32C3-MINI-1") (pin "P$19") (pinfunction "P$19_P$19") (pintype "bidirectional"))
      (node (ref "IO5") (pin "TP") (pinfunction "TP_TP") (pintype "input"))
    )
    (net (code "25") (name "Net-(ESP32C3-MINI-1-PadP$23)") (class "Default")
      (node (ref "ESP32C3-MINI-1") (pin "P$23") (pinfunction "P$23_P$23") (pintype "bidirectional"))
      (node (ref "IO9") (pin "TP") (pinfunction "TP_TP") (pintype "input"))
    )
    (net (code "26") (name "Net-(JPA-PadP$1)") (class "Default")
      (node (ref "JPA") (pin "P$1") (pinfunction "P$1_P$1") (pintype "bidirectional"))
      (node (ref "JPB") (pin "P$1") (pinfunction "P$1_P$1") (pintype "bidirectional"))
      (node (ref "R12") (pin "1") (pinfunction "1_1") (pintype "passive"))
      (node (ref "R13") (pin "2") (pinfunction "2_2") (pintype "passive"))
      (node (ref "R15") (pin "1") (pinfunction "1_1") (pintype "passive"))
      (node (ref "R17") (pin "2") (pinfunction "2_2") (pintype "passive"))
      (node (ref "R36") (pin "1") (pinfunction "1_1") (pintype "passive"))
    )
    (net (code "27") (name "Net-(L1-2)") (class "Default")
      (node (ref "L1") (pin "P$2") (pinfunction "2_P$2") (pintype "passive"))
      (node (ref "U$17") (pin "3") (pinfunction "LX_3") (pintype "bidirectional"))
    )
    (net (code "28") (name "Net-(L2-1)") (class "Default")
      (node (ref "C24") (pin "1") (pinfunction "1_1") (pintype "passive"))
      (node (ref "L2") (pin "P$1") (pinfunction "1_P$1") (pintype "passive"))
      (node (ref "U$13") (pin "P$10") (pinfunction "LX_P$10") (pintype "bidirectional"))
    )
    (net (code "29") (name "Net-(R12-Pad2)") (class "Default")
      (node (ref "R12") (pin "2") (pinfunction "2_2") (pintype "passive"))
      (node (ref "R35") (pin "1") (pinfunction "1_1") (pintype "passive"))
      (node (ref "R36") (pin "2") (pinfunction "2_2") (pintype "passive"))
    )
    (net (code "30") (name "Net-(T1-B)") (class "Default")
      (node (ref "R6") (pin "1") (pinfunction "1_1") (pintype "passive"))
      (node (ref "T1") (pin "1") (pinfunction "B_1") (pintype "passive"))
    )
    (net (code "31") (name "Net-(U$1-24-XIN)") (class "Default")
      (node (ref "C9") (pin "2") (pinfunction "2_2") (pintype "passive"))
      (node (ref "Q1") (pin "3") (pinfunction "3_3") (pintype "passive"))
      (node (ref "R1") (pin "1") (pinfunction "1_1") (pintype "passive"))
      (node (ref "U$1") (pin "P$24") (pinfunction "24-XIN_P$24") (pintype "bidirectional"))
    )
    (net (code "32") (name "Net-(U$1-25-XOUT)") (class "Default")
      (node (ref "C8") (pin "2") (pinfunction "2_2") (pintype "passive"))
      (node (ref "Q1") (pin "1") (pinfunction "1_1") (pintype "passive"))
      (node (ref "R1") (pin "2") (pinfunction "2_2") (pintype "passive"))
      (node (ref "U$1") (pin "P$25") (pinfunction "25-XOUT_P$25") (pintype "bidirectional"))
    )
    (net (code "33") (name "Net-(U$1-26-CI)") (class "Default")
      (node (ref "R4") (pin "2") (pinfunction "2_2") (pintype "passive"))
      (node (ref "R5") (pin "1") (pinfunction "1_1") (pintype "passive"))
      (node (ref "U$1") (pin "P$26") (pinfunction "26-CI_P$26") (pintype "bidirectional"))
    )
    (net (code "34") (name "Net-(U$1-31-RST_N)") (class "Default")
      (node (ref "R2") (pin "2") (pinfunction "2_2") (pintype "passive"))
      (node (ref "R3") (pin "1") (pinfunction "1_1") (pintype "passive"))
      (node (ref "U$1") (pin "P$31") (pinfunction "31-RST_N_P$31") (pintype "bidirectional"))
    )
    (net (code "35") (name "Net-(U$1-BO-2)") (class "Default")
      (node (ref "U$1") (pin "P$2") (pinfunction "BO-2_P$2") (pintype "output"))
      (node (ref "U$30") (pin "P$2") (pinfunction "P$2_P$2") (pintype "bidirectional"))
    )
    (net (code "36") (name "Net-(U$1-CLKO-6)") (class "Default")
      (node (ref "C1") (pin "1") (pinfunction "1_1") (pintype "passive"))
      (node (ref "U$1") (pin "P$6") (pinfunction "CLKO-6_P$6") (pintype "bidirectional"))
    )
    (net (code "37") (name "Net-(U$1-CO-5)") (class "Default")
      (node (ref "U$1") (pin "P$5") (pinfunction "CO-5_P$5") (pintype "bidirectional"))
      (node (ref "U$32") (pin "P$2") (pinfunction "P$2_P$2") (pintype "bidirectional"))
    )
    (net (code "38") (name "Net-(U$1-NRSTO-1)") (class "Default")
      (node (ref "U$1") (pin "P$1") (pinfunction "NRSTO-1_P$1") (pintype "output"))
      (node (ref "U$29") (pin "P$2") (pinfunction "P$2_P$2") (pintype "bidirectional"))
    )
    (net (code "39") (name "Net-(U$1-PLL_VDD-8)") (class "Default")
      (node (ref "C14") (pin "1") (pinfunction "1_1") (pintype "passive"))
      (node (ref "R33") (pin "1") (pinfunction "1_1") (pintype "passive"))
      (node (ref "R34") (pin "1") (pinfunction "1_1") (pintype "passive"))
      (node (ref "U$1") (pin "P$8") (pinfunction "PLL_VDD-8_P$8") (pintype "bidirectional"))
      (node (ref "U$1") (pin "P$9") (pinfunction "VDDIO-9_P$9") (pintype "bidirectional"))
    )
    (net (code "40") (name "Net-(U$1-RI-4)") (class "Default")
      (node (ref "U$1") (pin "P$4") (pinfunction "RI-4_P$4") (pintype "bidirectional"))
      (node (ref "U$31") (pin "P$2") (pinfunction "P$2_P$2") (pintype "bidirectional"))
    )
    (net (code "41") (name "Net-(U$2-24-XIN)") (class "Default")
      (node (ref "C1") (pin "2") (pinfunction "2_2") (pintype "passive"))
      (node (ref "U$2") (pin "P$24") (pinfunction "24-XIN_P$24") (pintype "bidirectional"))
    )
    (net (code "42") (name "Net-(U$2-26-CI)") (class "Default")
      (node (ref "U$2") (pin "P$26") (pinfunction "26-CI_P$26") (pintype "bidirectional"))
      (node (ref "U$32") (pin "P$1") (pinfunction "P$1_P$1") (pintype "bidirectional"))
    )
    (net (code "43") (name "Net-(U$2-28-RO)") (class "Default")
      (node (ref "U$2") (pin "P$28") (pinfunction "28-RO_P$28") (pintype "bidirectional"))
      (node (ref "U$31") (pin "P$1") (pinfunction "P$1_P$1") (pintype "bidirectional"))
    )
    (net (code "44") (name "Net-(U$2-29-BI)") (class "Default")
      (node (ref "U$2") (pin "P$29") (pinfunction "29-BI_P$29") (pintype "bidirectional"))
      (node (ref "U$30") (pin "P$1") (pinfunction "P$1_P$1") (pintype "bidirectional"))
    )
    (net (code "45") (name "Net-(U$2-31-RST_N)") (class "Default")
      (node (ref "U$2") (pin "P$31") (pinfunction "31-RST_N_P$31") (pintype "bidirectional"))
      (node (ref "U$29") (pin "P$1") (pinfunction "P$1_P$1") (pintype "bidirectional"))
    )
    (net (code "46") (name "Net-(U$2-BO-2)") (class "Default")
      (node (ref "U$2") (pin "P$2") (pinfunction "BO-2_P$2") (pintype "output"))
      (node (ref "U$25") (pin "P$2") (pinfunction "P$2_P$2") (pintype "bidirectional"))
    )
    (net (code "47") (name "Net-(U$2-CLKO-6)") (class "Default")
      (node (ref "C2") (pin "1") (pinfunction "1_1") (pintype "passive"))
      (node (ref "U$2") (pin "P$6") (pinfunction "CLKO-6_P$6") (pintype "bidirectional"))
    )
    (net (code "48") (name "Net-(U$2-CO-5)") (class "Default")
      (node (ref "U$2") (pin "P$5") (pinfunction "CO-5_P$5") (pintype "bidirectional"))
      (node (ref "U$28") (pin "P$2") (pinfunction "P$2_P$2") (pintype "bidirectional"))
    )
    (net (code "49") (name "Net-(U$2-NRSTO-1)") (class "Default")
      (node (ref "U$2") (pin "P$1") (pinfunction "NRSTO-1_P$1") (pintype "output"))
      (node (ref "U$24") (pin "P$2") (pinfunction "P$2_P$2") (pintype "bidirectional"))
    )
    (net (code "50") (name "Net-(U$2-PLL_VDD-8)") (class "Default")
      (node (ref "C15") (pin "1") (pinfunction "1_1") (pintype "passive"))
      (node (ref "R31") (pin "1") (pinfunction "1_1") (pintype "passive"))
      (node (ref "R32") (pin "1") (pinfunction "1_1") (pintype "passive"))
      (node (ref "U$2") (pin "P$8") (pinfunction "PLL_VDD-8_P$8") (pintype "bidirectional"))
      (node (ref "U$2") (pin "P$9") (pinfunction "VDDIO-9_P$9") (pintype "bidirectional"))
    )
    (net (code "51") (name "Net-(U$2-RI-4)") (class "Default")
      (node (ref "U$2") (pin "P$4") (pinfunction "RI-4_P$4") (pintype "bidirectional"))
      (node (ref "U$26") (pin "P$2") (pinfunction "P$2_P$2") (pintype "bidirectional"))
    )
    (net (code "52") (name "Net-(U$3-24-XIN)") (class "Default")
      (node (ref "C2") (pin "2") (pinfunction "2_2") (pintype "passive"))
      (node (ref "U$3") (pin "P$24") (pinfunction "24-XIN_P$24") (pintype "bidirectional"))
    )
    (net (code "53") (name "Net-(U$3-26-CI)") (class "Default")
      (node (ref "U$28") (pin "P$1") (pinfunction "P$1_P$1") (pintype "bidirectional"))
      (node (ref "U$3") (pin "P$26") (pinfunction "26-CI_P$26") (pintype "bidirectional"))
    )
    (net (code "54") (name "Net-(U$3-28-RO)") (class "Default")
      (node (ref "U$26") (pin "P$1") (pinfunction "P$1_P$1") (pintype "bidirectional"))
      (node (ref "U$3") (pin "P$28") (pinfunction "28-RO_P$28") (pintype "bidirectional"))
    )
    (net (code "55") (name "Net-(U$3-29-BI)") (class "Default")
      (node (ref "U$25") (pin "P$1") (pinfunction "P$1_P$1") (pintype "bidirectional"))
      (node (ref "U$3") (pin "P$29") (pinfunction "29-BI_P$29") (pintype "bidirectional"))
    )
    (net (code "56") (name "Net-(U$3-31-RST_N)") (class "Default")
      (node (ref "U$24") (pin "P$1") (pinfunction "P$1_P$1") (pintype "bidirectional"))
      (node (ref "U$3") (pin "P$31") (pinfunction "31-RST_N_P$31") (pintype "bidirectional"))
    )
    (net (code "57") (name "Net-(U$3-BO-2)") (class "Default")
      (node (ref "U$21") (pin "P$2") (pinfunction "P$2_P$2") (pintype "bidirectional"))
      (node (ref "U$3") (pin "P$2") (pinfunction "BO-2_P$2") (pintype "output"))
    )
    (net (code "58") (name "Net-(U$3-CLKO-6)") (class "Default")
      (node (ref "C3") (pin "1") (pinfunction "1_1") (pintype "passive"))
      (node (ref "U$3") (pin "P$6") (pinfunction "CLKO-6_P$6") (pintype "bidirectional"))
    )
    (net (code "59") (name "Net-(U$3-CO-5)") (class "Default")
      (node (ref "U$23") (pin "P$2") (pinfunction "P$2_P$2") (pintype "bidirectional"))
      (node (ref "U$3") (pin "P$5") (pinfunction "CO-5_P$5") (pintype "bidirectional"))
    )
    (net (code "60") (name "Net-(U$3-NRSTO-1)") (class "Default")
      (node (ref "U$20") (pin "P$2") (pinfunction "P$2_P$2") (pintype "bidirectional"))
      (node (ref "U$3") (pin "P$1") (pinfunction "NRSTO-1_P$1") (pintype "output"))
    )
    (net (code "61") (name "Net-(U$3-PLL_VDD-8)") (class "Default")
      (node (ref "C16") (pin "1") (pinfunction "1_1") (pintype "passive"))
      (node (ref "R29") (pin "1") (pinfunction "1_1") (pintype "passive"))
      (node (ref "R30") (pin "1") (pinfunction "1_1") (pintype "passive"))
      (node (ref "U$3") (pin "P$8") (pinfunction "PLL_VDD-8_P$8") (pintype "bidirectional"))
      (node (ref "U$3") (pin "P$9") (pinfunction "VDDIO-9_P$9") (pintype "bidirectional"))
    )
    (net (code "62") (name "Net-(U$3-RI-4)") (class "Default")
      (node (ref "U$22") (pin "P$2") (pinfunction "P$2_P$2") (pintype "bidirectional"))
      (node (ref "U$3") (pin "P$4") (pinfunction "RI-4_P$4") (pintype "bidirectional"))
    )
    (net (code "63") (name "Net-(U$4-24-XIN)") (class "Default")
      (node (ref "C3") (pin "2") (pinfunction "2_2") (pintype "passive"))
      (node (ref "U$4") (pin "P$24") (pinfunction "24-XIN_P$24") (pintype "bidirectional"))
    )
    (net (code "64") (name "Net-(U$4-26-CI)") (class "Default")
      (node (ref "U$23") (pin "P$1") (pinfunction "P$1_P$1") (pintype "bidirectional"))
      (node (ref "U$4") (pin "P$26") (pinfunction "26-CI_P$26") (pintype "bidirectional"))
    )
    (net (code "65") (name "Net-(U$4-28-RO)") (class "Default")
      (node (ref "U$22") (pin "P$1") (pinfunction "P$1_P$1") (pintype "bidirectional"))
      (node (ref "U$4") (pin "P$28") (pinfunction "28-RO_P$28") (pintype "bidirectional"))
    )
    (net (code "66") (name "Net-(U$4-29-BI)") (class "Default")
      (node (ref "U$21") (pin "P$1") (pinfunction "P$1_P$1") (pintype "bidirectional"))
      (node (ref "U$4") (pin "P$29") (pinfunction "29-BI_P$29") (pintype "bidirectional"))
    )
    (net (code "67") (name "Net-(U$4-31-RST_N)") (class "Default")
      (node (ref "U$20") (pin "P$1") (pinfunction "P$1_P$1") (pintype "bidirectional"))
      (node (ref "U$4") (pin "P$31") (pinfunction "31-RST_N_P$31") (pintype "bidirectional"))
    )
    (net (code "68") (name "Net-(U$4-PLL_VDD-8)") (class "Default")
      (node (ref "C17") (pin "1") (pinfunction "1_1") (pintype "passive"))
      (node (ref "R27") (pin "1") (pinfunction "1_1") (pintype "passive"))
      (node (ref "R28") (pin "1") (pinfunction "1_1") (pintype "passive"))
      (node (ref "U$4") (pin "P$8") (pinfunction "PLL_VDD-8_P$8") (pintype "bidirectional"))
      (node (ref "U$4") (pin "P$9") (pinfunction "VDDIO-9_P$9") (pintype "bidirectional"))
    )
    (net (code "69") (name "Net-(U$4-RI-4)") (class "Default")
      (node (ref "U$15") (pin "1") (pinfunction "1_1") (pintype "passive"))
      (node (ref "U$4") (pin "P$4") (pinfunction "RI-4_P$4") (pintype "bidirectional"))
    )
    (net (code "70") (name "Net-(U$13-BS)") (class "Default")
      (node (ref "C24") (pin "2") (pinfunction "2_2") (pintype "passive"))
      (node (ref "U$13") (pin "P$6") (pinfunction "BS_P$6") (pintype "bidirectional"))
    )
    (net (code "71") (name "Net-(U$13-FB)") (class "Default")
      (node (ref "JPA") (pin "P$2") (pinfunction "P$2_P$2") (pintype "bidirectional"))
      (node (ref "U$13") (pin "P$4") (pinfunction "FB_P$4") (pintype "bidirectional"))
    )
    (net (code "72") (name "Net-(U$13-VCC)") (class "Default")
      (node (ref "C25") (pin "1") (pinfunction "1_1") (pintype "passive"))
      (node (ref "R15") (pin "2") (pinfunction "2_2") (pintype "passive"))
      (node (ref "U$13") (pin "P$5") (pinfunction "VCC_P$5") (pintype "bidirectional"))
    )
    (net (code "73") (name "Net-(U$16-P$2A5)") (class "Default")
      (node (ref "R22") (pin "1") (pinfunction "1_1") (pintype "passive"))
      (node (ref "U$16") (pin "P$203A5") (pinfunction "P$2A5_P$203A5") (pintype "bidirectional"))
    )
    (net (code "74") (name "Net-(U$16-P$3B5)") (class "Default")
      (node (ref "R16") (pin "1") (pinfunction "1_1") (pintype "passive"))
      (node (ref "U$16") (pin "P$210B5") (pinfunction "P$3B5_P$210B5") (pintype "bidirectional"))
    )
    (net (code "75") (name "Net-(U$17-FB)") (class "Default")
      (node (ref "R23") (pin "2") (pinfunction "2_2") (pintype "passive"))
      (node (ref "R24") (pin "2") (pinfunction "2_2") (pintype "passive"))
      (node (ref "U$17") (pin "6") (pinfunction "FB_6") (pintype "bidirectional"))
    )
    (net (code "76") (name "VCC_1") (class "Default")
      (node (ref "C11") (pin "2") (pinfunction "2_2") (pintype "passive"))
      (node (ref "C15") (pin "2") (pinfunction "2_2") (pintype "passive"))
      (node (ref "C18") (pin "2") (pinfunction "2_2") (pintype "passive"))
      (node (ref "C19") (pin "1") (pinfunction "1_1") (pintype "passive"))
      (node (ref "C4") (pin "1") (pinfunction "1_1") (pintype "passive"))
      (node (ref "R10") (pin "2") (pinfunction "2_2") (pintype "passive"))
      (node (ref "R11") (pin "1") (pinfunction "1_1") (pintype "passive"))
      (node (ref "R31") (pin "2") (pinfunction "2_2") (pintype "passive"))
      (node (ref "U$1") (pin "P$33") (pinfunction "34-VDDX_P$33") (pintype "bidirectional"))
      (node (ref "U$10") (pin "P$2") (pinfunction "C_P$2") (pintype "passive"))
      (node (ref "U$2") (pin "P$19") (pinfunction "19-TEST_P$19") (pintype "bidirectional"))
      (node (ref "U$2") (pin "P$20") (pinfunction "20-ADDR0_P$20") (pintype "bidirectional"))
      (node (ref "U$2") (pin "P$21") (pinfunction "21-ADDR1_P$21") (pintype "bidirectional"))
      (node (ref "U$2") (pin "P$22") (pinfunction "22-ADDR2_P$22") (pintype "bidirectional"))
      (node (ref "U$2") (pin "P$23") (pinfunction "23-ADDR3_P$23") (pintype "bidirectional"))
      (node (ref "U$2") (pin "P$3") (pinfunction "RI_A-3_P$3") (pintype "bidirectional"))
      (node (ref "U$2") (pin "P$34") (pinfunction "33-GNDX_P$34") (pintype "bidirectional"))
      (node (ref "U$2") (pin "P$7") (pinfunction "PLL_VSS-7_P$7") (pintype "bidirectional"))
      (node (ref "U$6") (pin "1") (pinfunction "VSS_1") (pintype "bidirectional"))
      (node (ref "U$9") (pin "P$1") (pinfunction "A_P$1") (pintype "passive"))
    )
    (net (code "77") (name "VCC_2") (class "Default")
      (node (ref "C12") (pin "2") (pinfunction "2_2") (pintype "passive"))
      (node (ref "C16") (pin "2") (pinfunction "2_2") (pintype "passive"))
      (node (ref "C19") (pin "2") (pinfunction "2_2") (pintype "passive"))
      (node (ref "C20") (pin "1") (pinfunction "1_1") (pintype "passive"))
      (node (ref "C5") (pin "1") (pinfunction "1_1") (pintype "passive"))
      (node (ref "R10") (pin "1") (pinfunction "1_1") (pintype "passive"))
      (node (ref "R29") (pin "2") (pinfunction "2_2") (pintype "passive"))
      (node (ref "R9") (pin "2") (pinfunction "2_2") (pintype "passive"))
      (node (ref "U$10") (pin "P$1") (pinfunction "A_P$1") (pintype "passive"))
      (node (ref "U$11") (pin "P$2") (pinfunction "C_P$2") (pintype "passive"))
      (node (ref "U$2") (pin "P$33") (pinfunction "34-VDDX_P$33") (pintype "bidirectional"))
      (node (ref "U$3") (pin "P$19") (pinfunction "19-TEST_P$19") (pintype "bidirectional"))
      (node (ref "U$3") (pin "P$20") (pinfunction "20-ADDR0_P$20") (pintype "bidirectional"))
      (node (ref "U$3") (pin "P$21") (pinfunction "21-ADDR1_P$21") (pintype "bidirectional"))
      (node (ref "U$3") (pin "P$22") (pinfunction "22-ADDR2_P$22") (pintype "bidirectional"))
      (node (ref "U$3") (pin "P$23") (pinfunction "23-ADDR3_P$23") (pintype "bidirectional"))
      (node (ref "U$3") (pin "P$3") (pinfunction "RI_A-3_P$3") (pintype "bidirectional"))
      (node (ref "U$3") (pin "P$34") (pinfunction "33-GNDX_P$34") (pintype "bidirectional"))
      (node (ref "U$3") (pin "P$7") (pinfunction "PLL_VSS-7_P$7") (pintype "bidirectional"))
      (node (ref "U$7") (pin "1") (pinfunction "VSS_1") (pintype "bidirectional"))
    )
    (net (code "78") (name "VCC_3") (class "Default")
      (node (ref "C13") (pin "2") (pinfunction "2_2") (pintype "passive"))
      (node (ref "C17") (pin "2") (pinfunction "2_2") (pintype "passive"))
      (node (ref "C20") (pin "2") (pinfunction "2_2") (pintype "passive"))
      (node (ref "C21") (pin "1") (pinfunction "1_1") (pintype "passive"))
      (node (ref "C6") (pin "1") (pinfunction "1_1") (pintype "passive"))
      (node (ref "R27") (pin "2") (pinfunction "2_2") (pintype "passive"))
      (node (ref "R9") (pin "1") (pinfunction "1_1") (pintype "passive"))
      (node (ref "U$11") (pin "P$1") (pinfunction "A_P$1") (pintype "passive"))
      (node (ref "U$12") (pin "P$2") (pinfunction "C_P$2") (pintype "passive"))
      (node (ref "U$3") (pin "P$33") (pinfunction "34-VDDX_P$33") (pintype "bidirectional"))
      (node (ref "U$4") (pin "P$19") (pinfunction "19-TEST_P$19") (pintype "bidirectional"))
      (node (ref "U$4") (pin "P$20") (pinfunction "20-ADDR0_P$20") (pintype "bidirectional"))
      (node (ref "U$4") (pin "P$21") (pinfunction "21-ADDR1_P$21") (pintype "bidirectional"))
      (node (ref "U$4") (pin "P$22") (pinfunction "22-ADDR2_P$22") (pintype "bidirectional"))
      (node (ref "U$4") (pin "P$23") (pinfunction "23-ADDR3_P$23") (pintype "bidirectional"))
      (node (ref "U$4") (pin "P$3") (pinfunction "RI_A-3_P$3") (pintype "bidirectional"))
      (node (ref "U$4") (pin "P$34") (pinfunction "33-GNDX_P$34") (pintype "bidirectional"))
      (node (ref "U$4") (pin "P$7") (pinfunction "PLL_VSS-7_P$7") (pintype "bidirectional"))
      (node (ref "U$8") (pin "1") (pinfunction "VSS_1") (pintype "bidirectional"))
    )
    (net (code "79") (name "unconnected-(D1-PadDO)") (class "Default")
      (node (ref "D1") (pin "DO") (pinfunction "DO_DO") (pintype "bidirectional"))
    )
    (net (code "80") (name "unconnected-(ESP32C3-MINI-1-PadP$4)") (class "Default")
      (node (ref "ESP32C3-MINI-1") (pin "P$4") (pinfunction "P$4_P$4") (pintype "bidirectional"))
    )
    (net (code "81") (name "unconnected-(ESP32C3-MINI-1-PadP$6)") (class "Default")
      (node (ref "ESP32C3-MINI-1") (pin "P$6") (pinfunction "P$6_P$6") (pintype "bidirectional"))
    )
    (net (code "82") (name "unconnected-(ESP32C3-MINI-1-PadP$7)") (class "Default")
      (node (ref "ESP32C3-MINI-1") (pin "P$7") (pinfunction "P$7_P$7") (pintype "bidirectional"))
    )
    (net (code "83") (name "unconnected-(ESP32C3-MINI-1-PadP$9)") (class "Default")
      (node (ref "ESP32C3-MINI-1") (pin "P$9") (pinfunction "P$9_P$9") (pintype "bidirectional"))
    )
    (net (code "84") (name "unconnected-(ESP32C3-MINI-1-PadP$10)") (class "Default")
      (node (ref "ESP32C3-MINI-1") (pin "P$10") (pinfunction "P$10_P$10") (pintype "bidirectional"))
    )
    (net (code "85") (name "unconnected-(ESP32C3-MINI-1-PadP$13)") (class "Default")
      (node (ref "ESP32C3-MINI-1") (pin "P$13") (pinfunction "P$13_P$13") (pintype "bidirectional"))
    )
    (net (code "86") (name "unconnected-(ESP32C3-MINI-1-PadP$14)") (class "Default")
      (node (ref "ESP32C3-MINI-1") (pin "P$14") (pinfunction "P$14_P$14") (pintype "bidirectional"))
    )
    (net (code "87") (name "unconnected-(ESP32C3-MINI-1-PadP$15)") (class "Default")
      (node (ref "ESP32C3-MINI-1") (pin "P$15") (pinfunction "P$15_P$15") (pintype "bidirectional"))
    )
    (net (code "88") (name "unconnected-(ESP32C3-MINI-1-PadP$17)") (class "Default")
      (node (ref "ESP32C3-MINI-1") (pin "P$17") (pinfunction "P$17_P$17") (pintype "bidirectional"))
    )
    (net (code "89") (name "unconnected-(ESP32C3-MINI-1-PadP$20)") (class "Default")
      (node (ref "ESP32C3-MINI-1") (pin "P$20") (pinfunction "P$20_P$20") (pintype "bidirectional"))
    )
    (net (code "90") (name "unconnected-(ESP32C3-MINI-1-PadP$24)") (class "Default")
      (node (ref "ESP32C3-MINI-1") (pin "P$24") (pinfunction "P$24_P$24") (pintype "bidirectional"))
    )
    (net (code "91") (name "unconnected-(ESP32C3-MINI-1-PadP$25)") (class "Default")
      (node (ref "ESP32C3-MINI-1") (pin "P$25") (pinfunction "P$25_P$25") (pintype "bidirectional"))
    )
    (net (code "92") (name "unconnected-(ESP32C3-MINI-1-PadP$28)") (class "Default")
      (node (ref "ESP32C3-MINI-1") (pin "P$28") (pinfunction "P$28_P$28") (pintype "bidirectional"))
    )
    (net (code "93") (name "unconnected-(ESP32C3-MINI-1-PadP$29)") (class "Default")
      (node (ref "ESP32C3-MINI-1") (pin "P$29") (pinfunction "P$29_P$29") (pintype "bidirectional"))
    )
    (net (code "94") (name "unconnected-(ESP32C3-MINI-1-PadP$32)") (class "Default")
      (node (ref "ESP32C3-MINI-1") (pin "P$32") (pinfunction "P$32_P$32") (pintype "bidirectional"))
    )
    (net (code "95") (name "unconnected-(ESP32C3-MINI-1-PadP$33)") (class "Default")
      (node (ref "ESP32C3-MINI-1") (pin "P$33") (pinfunction "P$33_P$33") (pintype "bidirectional"))
    )
    (net (code "96") (name "unconnected-(ESP32C3-MINI-1-PadP$34)") (class "Default")
      (node (ref "ESP32C3-MINI-1") (pin "P$34") (pinfunction "P$34_P$34") (pintype "bidirectional"))
    )
    (net (code "97") (name "unconnected-(ESP32C3-MINI-1-PadP$35)") (class "Default")
      (node (ref "ESP32C3-MINI-1") (pin "P$35") (pinfunction "P$35_P$35") (pintype "bidirectional"))
    )
    (net (code "98") (name "unconnected-(Q1-Pad2)") (class "Default")
      (node (ref "Q1") (pin "2") (pinfunction "2_2") (pintype "passive"))
    )
    (net (code "99") (name "unconnected-(Q1-Pad4)") (class "Default")
      (node (ref "Q1") (pin "4") (pinfunction "4_4") (pintype "passive"))
    )
    (net (code "100") (name "unconnected-(U$1-17-RF-PadP$17)") (class "Default")
      (node (ref "U$1") (pin "P$17") (pinfunction "17-RF_P$17") (pintype "bidirectional"))
    )
    (net (code "101") (name "unconnected-(U$1-18-TF-PadP$18)") (class "Default")
      (node (ref "U$1") (pin "P$18") (pinfunction "18-TF_P$18") (pintype "bidirectional"))
    )
    (net (code "102") (name "unconnected-(U$1-LDO18O-13-PadP$13)") (class "Default")
      (node (ref "U$1") (pin "P$13") (pinfunction "LDO18O-13_P$13") (pintype "bidirectional"))
    )
    (net (code "103") (name "unconnected-(U$1-LDO25I-14-PadP$14)") (class "Default")
      (node (ref "U$1") (pin "P$14") (pinfunction "LDO25I-14_P$14") (pintype "bidirectional"))
    )
    (net (code "104") (name "unconnected-(U$1-LDO_08O-10-PadP$10)") (class "Default")
      (node (ref "U$1") (pin "P$10") (pinfunction "LDO_08O-10_P$10") (pintype "bidirectional"))
    )
    (net (code "105") (name "unconnected-(U$1-TEMP_N-16-PadP$16)") (class "Default")
      (node (ref "U$1") (pin "P$16") (pinfunction "TEMP_N-16_P$16") (pintype "bidirectional"))
    )
    (net (code "106") (name "unconnected-(U$1-TEMP_P-15-PadP$15)") (class "Default")
      (node (ref "U$1") (pin "P$15") (pinfunction "TEMP_P-15_P$15") (pintype "bidirectional"))
    )
    (net (code "107") (name "unconnected-(U$2-17-RF-PadP$17)") (class "Default")
      (node (ref "U$2") (pin "P$17") (pinfunction "17-RF_P$17") (pintype "bidirectional"))
    )
    (net (code "108") (name "unconnected-(U$2-18-TF-PadP$18)") (class "Default")
      (node (ref "U$2") (pin "P$18") (pinfunction "18-TF_P$18") (pintype "bidirectional"))
    )
    (net (code "109") (name "unconnected-(U$2-25-XOUT-PadP$25)") (class "Default")
      (node (ref "U$2") (pin "P$25") (pinfunction "25-XOUT_P$25") (pintype "bidirectional"))
    )
    (net (code "110") (name "unconnected-(U$2-LDO18O-13-PadP$13)") (class "Default")
      (node (ref "U$2") (pin "P$13") (pinfunction "LDO18O-13_P$13") (pintype "bidirectional"))
    )
    (net (code "111") (name "unconnected-(U$2-LDO25I-14-PadP$14)") (class "Default")
      (node (ref "U$2") (pin "P$14") (pinfunction "LDO25I-14_P$14") (pintype "bidirectional"))
    )
    (net (code "112") (name "unconnected-(U$2-LDO_08O-10-PadP$10)") (class "Default")
      (node (ref "U$2") (pin "P$10") (pinfunction "LDO_08O-10_P$10") (pintype "bidirectional"))
    )
    (net (code "113") (name "unconnected-(U$2-TEMP_N-16-PadP$16)") (class "Default")
      (node (ref "U$2") (pin "P$16") (pinfunction "TEMP_N-16_P$16") (pintype "bidirectional"))
    )
    (net (code "114") (name "unconnected-(U$2-TEMP_P-15-PadP$15)") (class "Default")
      (node (ref "U$2") (pin "P$15") (pinfunction "TEMP_P-15_P$15") (pintype "bidirectional"))
    )
    (net (code "115") (name "unconnected-(U$3-17-RF-PadP$17)") (class "Default")
      (node (ref "U$3") (pin "P$17") (pinfunction "17-RF_P$17") (pintype "bidirectional"))
    )
    (net (code "116") (name "unconnected-(U$3-18-TF-PadP$18)") (class "Default")
      (node (ref "U$3") (pin "P$18") (pinfunction "18-TF_P$18") (pintype "bidirectional"))
    )
    (net (code "117") (name "unconnected-(U$3-25-XOUT-PadP$25)") (class "Default")
      (node (ref "U$3") (pin "P$25") (pinfunction "25-XOUT_P$25") (pintype "bidirectional"))
    )
    (net (code "118") (name "unconnected-(U$3-LDO18O-13-PadP$13)") (class "Default")
      (node (ref "U$3") (pin "P$13") (pinfunction "LDO18O-13_P$13") (pintype "bidirectional"))
    )
    (net (code "119") (name "unconnected-(U$3-LDO25I-14-PadP$14)") (class "Default")
      (node (ref "U$3") (pin "P$14") (pinfunction "LDO25I-14_P$14") (pintype "bidirectional"))
    )
    (net (code "120") (name "unconnected-(U$3-LDO_08O-10-PadP$10)") (class "Default")
      (node (ref "U$3") (pin "P$10") (pinfunction "LDO_08O-10_P$10") (pintype "bidirectional"))
    )
    (net (code "121") (name "unconnected-(U$3-TEMP_N-16-PadP$16)") (class "Default")
      (node (ref "U$3") (pin "P$16") (pinfunction "TEMP_N-16_P$16") (pintype "bidirectional"))
    )
    (net (code "122") (name "unconnected-(U$3-TEMP_P-15-PadP$15)") (class "Default")
      (node (ref "U$3") (pin "P$15") (pinfunction "TEMP_P-15_P$15") (pintype "bidirectional"))
    )
    (net (code "123") (name "unconnected-(U$4-17-RF-PadP$17)") (class "Default")
      (node (ref "U$4") (pin "P$17") (pinfunction "17-RF_P$17") (pintype "bidirectional"))
    )
    (net (code "124") (name "unconnected-(U$4-18-TF-PadP$18)") (class "Default")
      (node (ref "U$4") (pin "P$18") (pinfunction "18-TF_P$18") (pintype "bidirectional"))
    )
    (net (code "125") (name "unconnected-(U$4-25-XOUT-PadP$25)") (class "Default")
      (node (ref "U$4") (pin "P$25") (pinfunction "25-XOUT_P$25") (pintype "bidirectional"))
    )
    (net (code "126") (name "unconnected-(U$4-BO-2-PadP$2)") (class "Default")
      (node (ref "U$4") (pin "P$2") (pinfunction "BO-2_P$2") (pintype "output"))
    )
    (net (code "127") (name "unconnected-(U$4-CLKO-6-PadP$6)") (class "Default")
      (node (ref "U$4") (pin "P$6") (pinfunction "CLKO-6_P$6") (pintype "bidirectional"))
    )
    (net (code "128") (name "unconnected-(U$4-CO-5-PadP$5)") (class "Default")
      (node (ref "U$4") (pin "P$5") (pinfunction "CO-5_P$5") (pintype "bidirectional"))
    )
    (net (code "129") (name "unconnected-(U$4-LDO18O-13-PadP$13)") (class "Default")
      (node (ref "U$4") (pin "P$13") (pinfunction "LDO18O-13_P$13") (pintype "bidirectional"))
    )
    (net (code "130") (name "unconnected-(U$4-LDO25I-14-PadP$14)") (class "Default")
      (node (ref "U$4") (pin "P$14") (pinfunction "LDO25I-14_P$14") (pintype "bidirectional"))
    )
    (net (code "131") (name "unconnected-(U$4-LDO_08O-10-PadP$10)") (class "Default")
      (node (ref "U$4") (pin "P$10") (pinfunction "LDO_08O-10_P$10") (pintype "bidirectional"))
    )
    (net (code "132") (name "unconnected-(U$4-NRSTO-1-PadP$1)") (class "Default")
      (node (ref "U$4") (pin "P$1") (pinfunction "NRSTO-1_P$1") (pintype "output"))
    )
    (net (code "133") (name "unconnected-(U$4-TEMP_N-16-PadP$16)") (class "Default")
      (node (ref "U$4") (pin "P$16") (pinfunction "TEMP_N-16_P$16") (pintype "bidirectional"))
    )
    (net (code "134") (name "unconnected-(U$4-TEMP_P-15-PadP$15)") (class "Default")
      (node (ref "U$4") (pin "P$15") (pinfunction "TEMP_P-15_P$15") (pintype "bidirectional"))
    )
    (net (code "135") (name "unconnected-(U$13-PG-PadP$2)") (class "Default")
      (node (ref "U$13") (pin "P$2") (pinfunction "PG_P$2") (pintype "bidirectional"))
    )
    (net (code "136") (name "unconnected-(U$16-P$8A8-PadP$209A8)") (class "Default")
      (node (ref "U$16") (pin "P$209A8") (pinfunction "P$8A8_P$209A8") (pintype "bidirectional"))
    )
    (net (code "137") (name "unconnected-(U$16-P$9B8-PadP$202B8)") (class "Default")
      (node (ref "U$16") (pin "P$202B8") (pinfunction "P$9B8_P$202B8") (pintype "bidirectional"))
    )
    (net (code "138") (name "unconnected-(U$17-NC-Pad5)") (class "Default")
      (node (ref "U$17") (pin "5") (pinfunction "NC_5") (pintype "bidirectional"))
    )
  )
)
